# X_TRACK_PWR_V3_1.net
KiCad netlist of a schematic drawn in Altium Designer
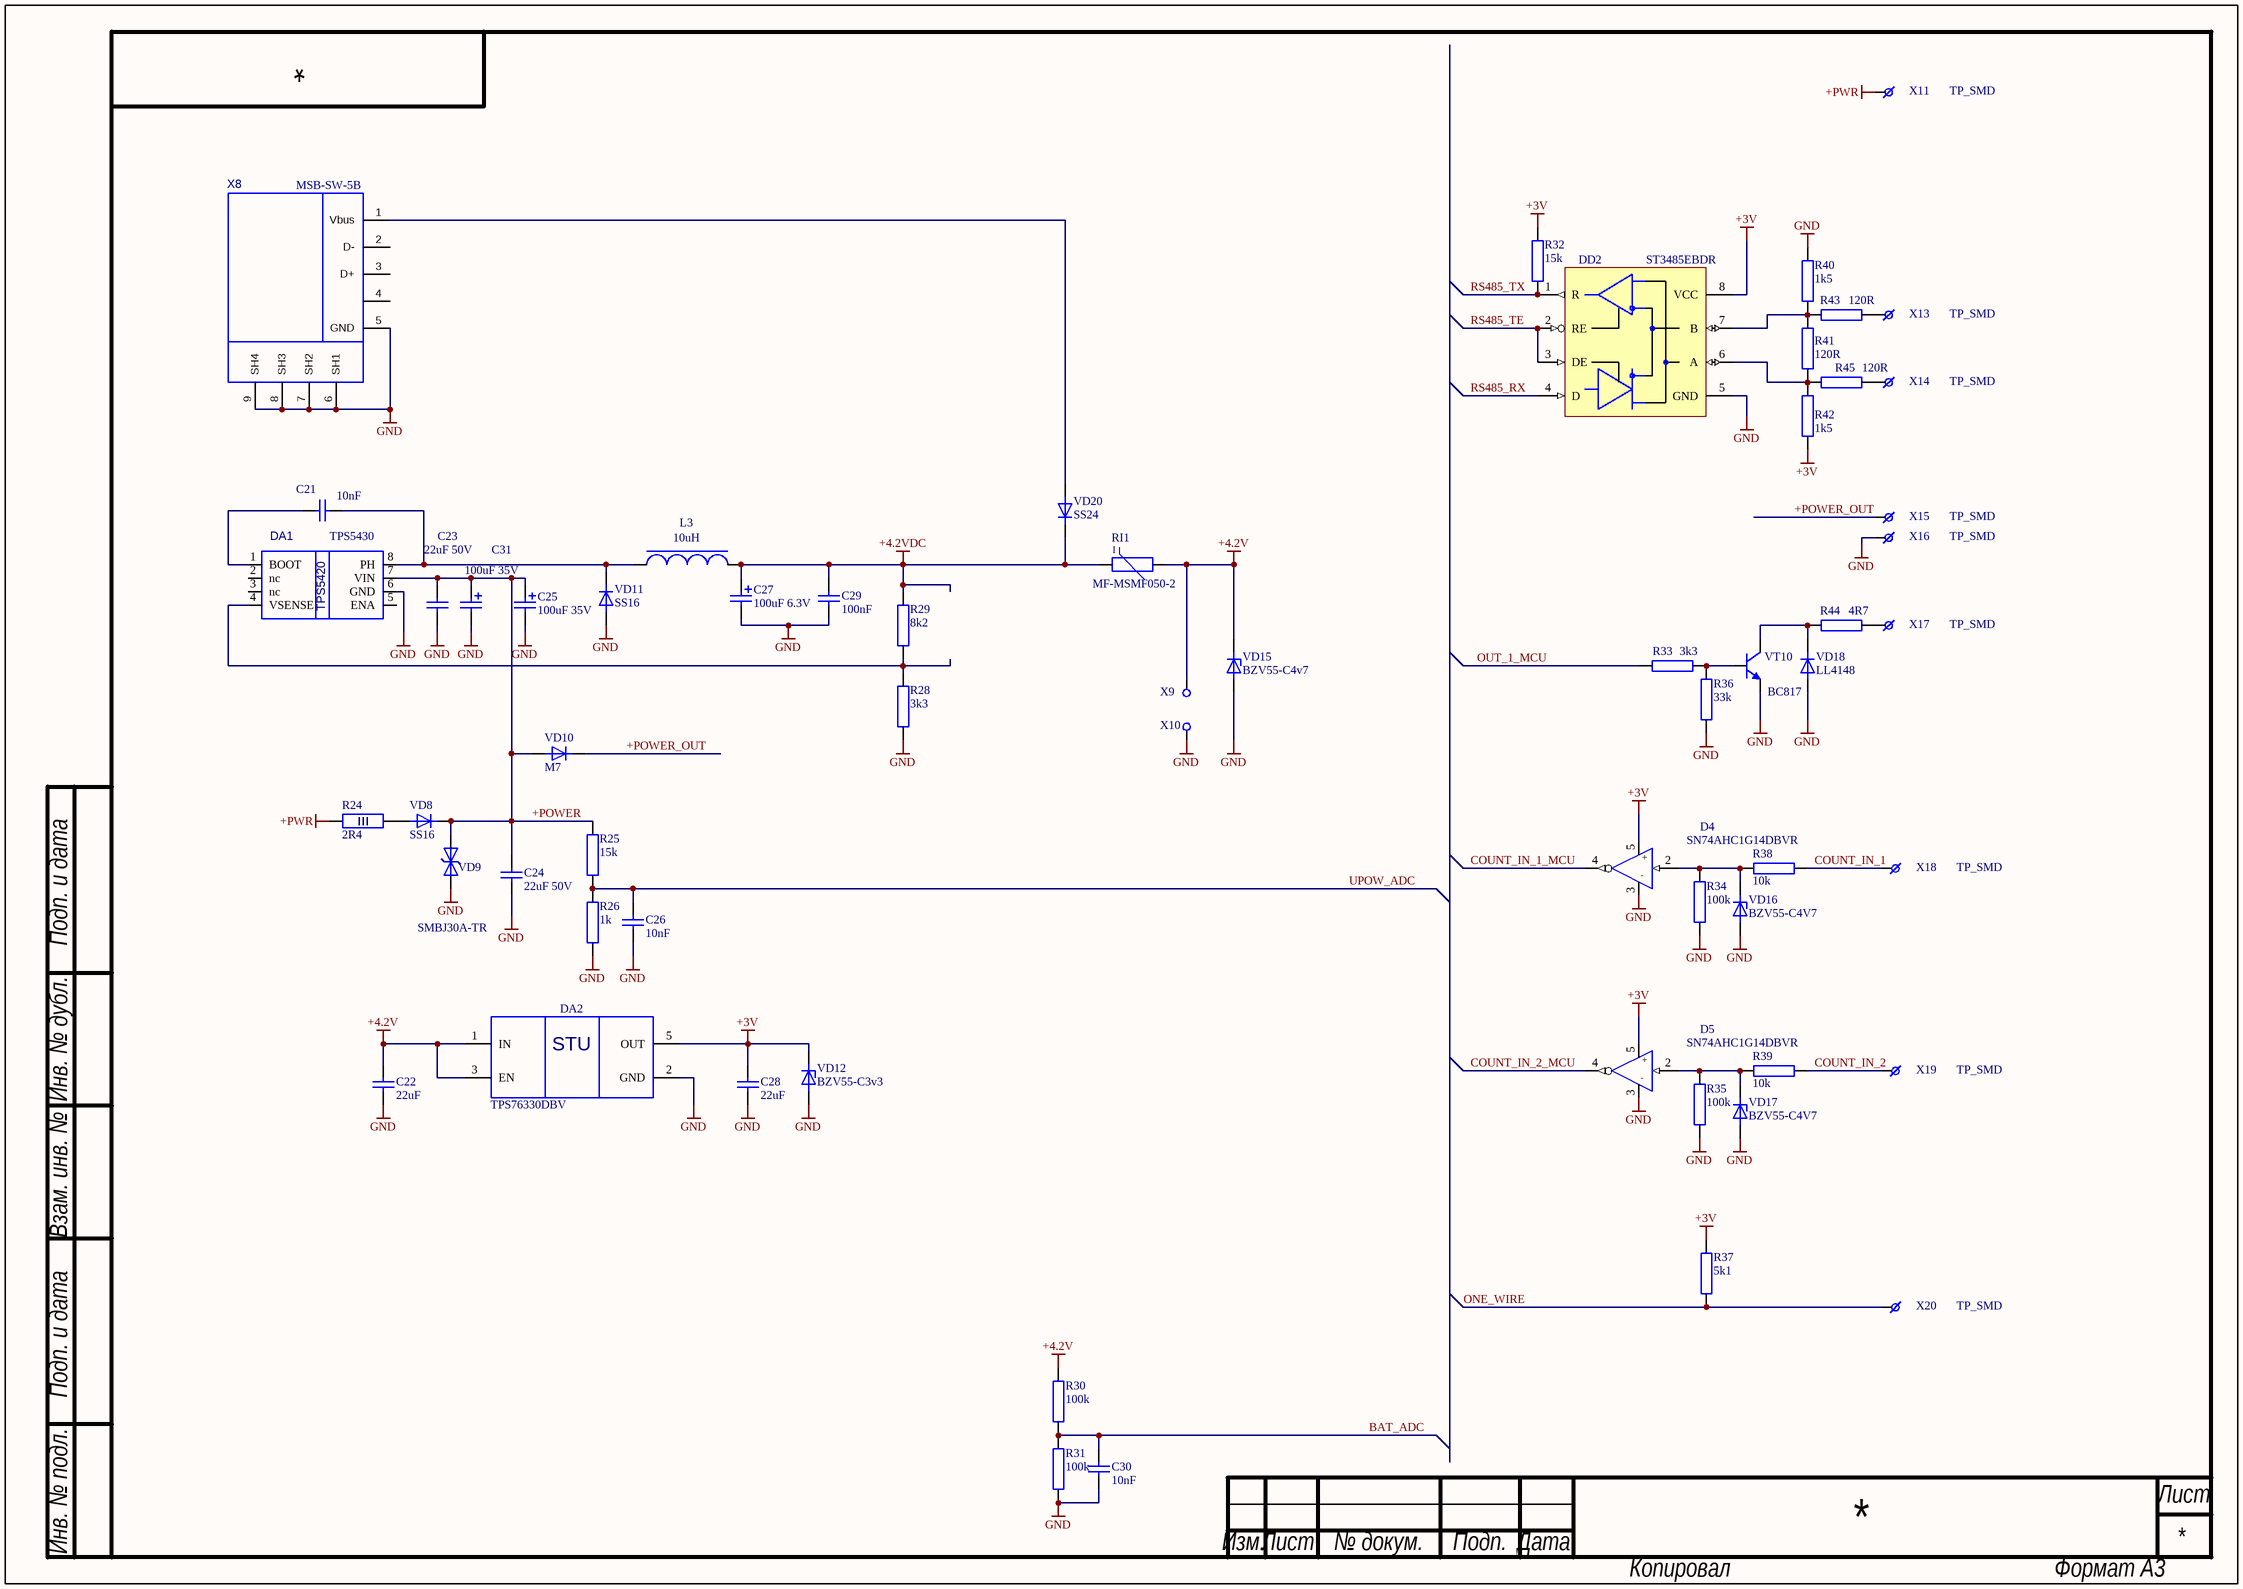
[diagram p0: X_TRACK_PWR V3.1.SchDoc]

(export (version "E")
  (design (tool "Eeschema 10.0.6"))
  (components
    (comp (ref "C21")
      (value "10nF")
      (footprint "CC0603")
      (description "Capacitor SMD 0603 X7R 10nF 20% 50V")
      (fields (field (name "MANUFACTURER") "Hitano") (field (name "Comment") "CC0603_10nF"))
      (libsource (lib "Ethernet_new_v000") (part "CC0603_10nF"))
    )
    (comp (ref "C22")
      (value "22uF")
      (footprint "CC0805")
      (description "Capacitor SMD 0805 Y5V 10uF 20% 16V")
      (fields (field (name "MANUFACTURER") "Hitano") (field (name "Comment") "CC0805_10uF"))
      (libsource (lib "Ethernet_new_v000") (part "CC0805_10uF"))
    )
    (comp (ref "C23")
      (value "22uF 50V")
      (footprint "CC1206")
      (description "Capacitor SMD 1206 X5R 10uF 20% 50V")
      (fields (field (name "MANUFACTURER") "Hitano") (field (name "Comment") "CC1206_10uF"))
      (libsource (lib "Ethernet_new_v000") (part "CC1206_10uF"))
    )
    (comp (ref "C24")
      (value "22uF 50V")
      (footprint "CC1206")
      (description "Capacitor SMD 1206 X5R 10uF 20% 50V")
      (fields (field (name "MANUFACTURER") "Hitano") (field (name "Comment") "CC1206_10uF"))
      (libsource (lib "Ethernet_new_v000") (part "CC1206_10uF"))
    )
    (comp (ref "C25")
      (value "100uF 35V")
      (footprint "CAPPR2.5-6.3X11.5 - HR")
      (description "Standard Capacitor polarized Radial leads, cylindrical aluminum case,")
      (fields (field (name "MANUFACTURER") "Hitano") (field (name "Comment") "C_ECR_100uF 35V_(D6)"))
      (libsource (lib "Ethernet_new_v000") (part "C_ECR_100uF 35V_(D6)"))
    )
    (comp (ref "C26")
      (value "10nF")
      (footprint "CC0603")
      (description "Capacitor SMD 0603 X7R 10nF 20% 50V")
      (fields (field (name "MANUFACTURER") "Hitano") (field (name "Comment") "CC0603_10nF"))
      (libsource (lib "Ethernet_new_v000") (part "CC0603_10nF"))
    )
    (comp (ref "C27")
      (value "100uF 6.3V")
      (footprint "6032_TC")
      (description "Capacitor tantall")
      (fields (field (name "MANUFACTURER") "AVX") (field (name "Comment") "C_TAJ 100uF 6.3V C"))
      (libsource (lib "Ethernet_new_v000") (part "C_TAJ 100uF 6.3V C"))
    )
    (comp (ref "C28")
      (value "22uF")
      (footprint "CC0805")
      (description "Capacitor SMD 0805 Y5V 10uF 20% 16V")
      (fields (field (name "MANUFACTURER") "Hitano") (field (name "Comment") "CC0805_10uF"))
      (libsource (lib "Ethernet_new_v000") (part "CC0805_10uF"))
    )
    (comp (ref "C29")
      (value "100nF")
      (footprint "CC0603")
      (description "Capacitor SMD 0603 X7R 100nF 20% 50V")
      (fields (field (name "MANUFACTURER") "Hitano") (field (name "Comment") "CC0603_100nF"))
      (libsource (lib "Ethernet_new_v000") (part "CC0603_100nF"))
    )
    (comp (ref "C30")
      (value "10nF")
      (footprint "CC0603")
      (description "Capacitor SMD 0603 X7R 10nF 20% 50V")
      (fields (field (name "MANUFACTURER") "Hitano") (field (name "Comment") "CC0603_10nF"))
      (libsource (lib "Ethernet_new_v000") (part "CC0603_10nF"))
    )
    (comp (ref "C31")
      (value "100uF 35V")
      (footprint "CAPPR2.5-6.3X11.5 - HL")
      (description "Standard Capacitor polarized Radial leads, cylindrical aluminum case,")
      (fields (field (name "MANUFACTURER") "Hitano") (field (name "Comment") "C_ECR_100uF 35V_(D6)"))
      (libsource (lib "Ethernet_new_v000") (part "C_ECR_100uF 35V_(D6)"))
    )
    (comp (ref "D4")
      (value "SN74AHC1G14DBVR")
      (footprint "SOT23-5AN")
      (description "SINGLE  SCHMITT-TRIGGER  INVERTER  GATE")
      (fields (field (name "MANUFACTURER") "Texas  Instruments"))
      (libsource (lib "Ethernet_new_v000") (part "SN74AHC1G14DBVR"))
    )
    (comp (ref "D5")
      (value "SN74AHC1G14DBVR")
      (footprint "SOT23-5AN")
      (description "SINGLE  SCHMITT-TRIGGER  INVERTER  GATE")
      (fields (field (name "MANUFACTURER") "Texas  Instruments"))
      (libsource (lib "Ethernet_new_v000") (part "SN74AHC1G14DBVR"))
    )
    (comp (ref "DA1")
      (value "TPS5430")
      (footprint "SO8")
      (description "TPS5420")
      (libsource (lib "V1.5") (part "TPS5420"))
    )
    (comp (ref "DA2")
      (value "TPS76330DBV")
      (footprint "SOT23-5")
      (libsource (lib "V1.5") (part "TPS76330DBV"))
    )
    (comp (ref "DD2")
      (value "ST3485EBDR")
      (footprint "8S1_L")
      (description "DRIVER RS-422/DIFFERENTIAL DRIVER AND RECEIVER PAIR")
      (fields (field (name "Comment") "SN75176"))
      (libsource (lib "Ethernet_new_v000") (part "SN75176"))
    )
    (comp (ref "L3")
      (value "10uH")
      (footprint "CDRH6D38")
      (description "CDRH6D38")
      (libsource (lib "V1.5") (part "CDRH6D38"))
    )
    (comp (ref "R24")
      (value "2R4")
      (footprint "MFR300- 3W-23-17.5X6.5")
      (description "Resistor  axial 3W")
      (fields (field (name "MANUFACTURER") "Uni-ohm") (field (name "Comment") "R_MFR03W"))
      (libsource (lib "Ethernet_new_v000") (part "R_MFR03W"))
    )
    (comp (ref "R25")
      (value "15k")
      (footprint "RC0603")
      (description "Resistor  SMD RC0603 5% 15k")
      (fields (field (name "MANUFACTURER") "Hitano") (field (name "Comment") "RC0603 15k"))
      (libsource (lib "Ethernet_new_v000") (part "RC0603 15k"))
    )
    (comp (ref "R26")
      (value "1k")
      (footprint "RC0603")
      (description "Resistor  SMD 0603  5% 1k")
      (fields (field (name "MANUFACTURER") "Hitano") (field (name "Comment") "RC0603 1k"))
      (libsource (lib "Ethernet_new_v000") (part "RC0603 1k"))
    )
    (comp (ref "R28")
      (value "3k3")
      (footprint "RC0603")
      (description "Resistor  SMD 0603  5% 3k3")
      (fields (field (name "MANUFACTURER") "Hitano") (field (name "Comment") "RC0603 3k3"))
      (libsource (lib "Ethernet_new_v000") (part "RC0603 3k3"))
    )
    (comp (ref "R29")
      (value "8k2")
      (footprint "RC0603")
      (description "Resistor  SMD 0603  5% 8k2")
      (fields (field (name "MANUFACTURER") "Hitano") (field (name "Comment") "RC0603 8k2"))
      (libsource (lib "Ethernet_new_v000") (part "RC0603 8k2"))
    )
    (comp (ref "R30")
      (value "100k")
      (footprint "RC0603")
      (description "Resistor  SMD 0603 5% 100k")
      (fields (field (name "MANUFACTURER") "Hitano") (field (name "Comment") "RC0603 100k"))
      (libsource (lib "Ethernet_new_v000") (part "RC0603 100k"))
    )
    (comp (ref "R31")
      (value "100k")
      (footprint "RC0603")
      (description "Resistor  SMD 0603 5% 100k")
      (fields (field (name "MANUFACTURER") "Hitano") (field (name "Comment") "RC0603 100k"))
      (libsource (lib "Ethernet_new_v000") (part "RC0603 100k"))
    )
    (comp (ref "R32")
      (value "15k")
      (footprint "RC0603")
      (description "Resistor  SMD RC0603 5% 15k")
      (fields (field (name "MANUFACTURER") "Hitano") (field (name "Comment") "RC0603 15k"))
      (libsource (lib "Ethernet_new_v000") (part "RC0603 15k"))
    )
    (comp (ref "R33")
      (value "3k3")
      (footprint "RC0603")
      (description "Resistor  SMD 0603  5% 3k3")
      (fields (field (name "MANUFACTURER") "Hitano") (field (name "Comment") "RC0603 3k3"))
      (libsource (lib "Ethernet_new_v000") (part "RC0603 3k3"))
    )
    (comp (ref "R34")
      (value "100k")
      (footprint "RC0603")
      (description "Resistor  SMD 0603 5% 100k")
      (fields (field (name "MANUFACTURER") "Hitano") (field (name "Comment") "RC0603 100k"))
      (libsource (lib "Ethernet_new_v000") (part "RC0603 100k"))
    )
    (comp (ref "R35")
      (value "100k")
      (footprint "RC0603")
      (description "Resistor  SMD 0603 5% 100k")
      (fields (field (name "MANUFACTURER") "Hitano") (field (name "Comment") "RC0603 100k"))
      (libsource (lib "Ethernet_new_v000") (part "RC0603 100k"))
    )
    (comp (ref "R36")
      (value "33k")
      (footprint "RC0603")
      (description "Resistor  SMD 0603 5% 33k")
      (fields (field (name "MANUFACTURER") "Hitano") (field (name "Comment") "RC0603 33k"))
      (libsource (lib "Ethernet_new_v000") (part "RC0603 33k"))
    )
    (comp (ref "R37")
      (value "5k1")
      (footprint "RC0603")
      (description "Resistor  SMD 0603 5% 5k1")
      (fields (field (name "MANUFACTURER") "Hitano") (field (name "Comment") "RC0603 5k1"))
      (libsource (lib "Ethernet_new_v000") (part "RC0603 5k1"))
    )
    (comp (ref "R38")
      (value "10k")
      (footprint "RC0603")
      (description "Resistor  SMD 0603 5% 4k7")
      (fields (field (name "MANUFACTURER") "Hitano") (field (name "Comment") "RC0603 4k7"))
      (libsource (lib "Ethernet_new_v000") (part "RC0603 4k7"))
    )
    (comp (ref "R39")
      (value "10k")
      (footprint "RC0603")
      (description "Resistor  SMD 0603 5% 4k7")
      (fields (field (name "MANUFACTURER") "Hitano") (field (name "Comment") "RC0603 4k7"))
      (libsource (lib "Ethernet_new_v000") (part "RC0603 4k7"))
    )
    (comp (ref "R40")
      (value "1k5")
      (footprint "RC0603")
      (description "Resistor  SMD 0603  5% 1k5")
      (fields (field (name "MANUFACTURER") "Hitano") (field (name "Comment") "RC0603 1k5"))
      (libsource (lib "Ethernet_new_v000") (part "RC0603 1k5"))
    )
    (comp (ref "R41")
      (value "120R")
      (footprint "RC0603")
      (description "Resistor  SMD 0603 5% 120R")
      (fields (field (name "MANUFACTURER") "Hitano") (field (name "Comment") "RC0603 120R"))
      (libsource (lib "Ethernet_new_v000") (part "RC0603 120R"))
    )
    (comp (ref "R42")
      (value "1k5")
      (footprint "RC0603")
      (description "Resistor  SMD 0603  5% 1k5")
      (fields (field (name "MANUFACTURER") "Hitano") (field (name "Comment") "RC0603 1k5"))
      (libsource (lib "Ethernet_new_v000") (part "RC0603 1k5"))
    )
    (comp (ref "R43")
      (value "120R")
      (footprint "RC0603")
      (description "Resistor  SMD 0603 5% 120R")
      (fields (field (name "MANUFACTURER") "Hitano") (field (name "Comment") "RC0603 120R"))
      (libsource (lib "Ethernet_new_v000") (part "RC0603 120R"))
    )
    (comp (ref "R44")
      (value "4R7")
      (footprint "RC0603")
      (description "Resistor  SMD 0603 5% 10R")
      (fields (field (name "MANUFACTURER") "Hitano") (field (name "Comment") "RC0603 10R"))
      (libsource (lib "Ethernet_new_v000") (part "RC0603 10R"))
    )
    (comp (ref "R45")
      (value "120R")
      (footprint "RC0603")
      (description "Resistor  SMD 0603 5% 120R")
      (fields (field (name "MANUFACTURER") "Hitano") (field (name "Comment") "RC0603 120R"))
      (libsource (lib "Ethernet_new_v000") (part "RC0603 120R"))
    )
    (comp (ref "RI1")
      (value "MF-MSMF050-2")
      (footprint "FSMD1812 Series")
      (description "Polymeric PTC resettable fuses")
      (fields (field (name "MANUFACTURER") "Fuzetech") (field (name "Comment") "POLY_PTS"))
      (libsource (lib "Ethernet_new_v000") (part "FSMD110-16"))
    )
    (comp (ref "VD8")
      (value "SS16")
      (footprint "SMA/DO-214AC")
      (description "SURFACE MOUNT GENERAL RECTIFIER")
      (fields (field (name "MANUFACTURER") "Suntan Technology Company Limited") (field (name "Comment") "M7"))
      (libsource (lib "Ethernet_new_v000") (part "M7"))
    )
    (comp (ref "VD9")
      (value "SMBJ30A-TR")
      (footprint "SMB/DO-214AA")
      (description "TRANSIENT VOLTAGE SUPPRESSORS")
      (fields (field (name "Comment") "Suppressor"))
      (libsource (lib "Ethernet_new_v000") (part "Suppressor"))
    )
    (comp (ref "VD10")
      (value "M7")
      (footprint "SMA/DO-214AC")
      (description "SURFACE MOUNT GENERAL RECTIFIER")
      (fields (field (name "MANUFACTURER") "Suntan Technology Company Limited"))
      (libsource (lib "Ethernet_new_v000") (part "M7"))
    )
    (comp (ref "VD11")
      (value "SS16")
      (footprint "SMB/DO-214AA")
      (description "SMD Diod 2A 40V")
      (fields (field (name "MANUFACTURER") "Vishay Semiconductors") (field (name "Comment") "SS24"))
      (libsource (lib "Ethernet_new_v000") (part "SS24"))
    )
    (comp (ref "VD12")
      (value "BZV55-C3v3")
      (footprint "SOD80D_C")
      (description "Zener diode")
      (fields (field (name "MANUFACTURER") "Philips") (field (name "Comment") "Zener"))
      (libsource (lib "Ethernet_new_v000") (part "Zener"))
    )
    (comp (ref "VD15")
      (value "BZV55-C4v7")
      (footprint "SOD80D_C")
      (description "Zener diode")
      (fields (field (name "MANUFACTURER") "Philips") (field (name "Comment") "Zener"))
      (libsource (lib "Ethernet_new_v000") (part "Zener"))
    )
    (comp (ref "VD16")
      (value "BZV55-C4V7")
      (footprint "SOD80D_C")
      (description "Zener diode")
      (fields (field (name "MANUFACTURER") "Philips") (field (name "Comment") "Zener"))
      (libsource (lib "Ethernet_new_v000") (part "Zener"))
    )
    (comp (ref "VD17")
      (value "BZV55-C4V7")
      (footprint "SOD80D_C")
      (description "Zener diode")
      (fields (field (name "MANUFACTURER") "Philips") (field (name "Comment") "Zener"))
      (libsource (lib "Ethernet_new_v000") (part "Zener"))
    )
    (comp (ref "VD18")
      (value "LL4148")
      (footprint "SOD80D_C")
      (description "SMD Diod LL4148")
      (fields (field (name "MANUFACTURER") "Fairchild Semiconductor"))
      (libsource (lib "Ethernet_new_v000") (part "LL4148"))
    )
    (comp (ref "VD20")
      (value "SS24")
      (footprint "SMB/DO-214AA")
      (description "SMD Diod 2A 40V")
      (fields (field (name "MANUFACTURER") "Vishay Semiconductors"))
      (libsource (lib "Ethernet_new_v000") (part "SS24"))
    )
    (comp (ref "VT10")
      (value "BC817")
      (footprint "SOT23")
      (description "NPN general-purpose transistors, 45V, 500mA")
      (fields (field (name "MANUFACTURER") "Philips"))
      (libsource (lib "Ethernet_new_v000") (part "BC817"))
    )
    (comp (ref "X8") (value "MSB-SW-5B") (footprint "MSB-SW-5B") (libsource (lib "V1.5") (part "MSB-SW-5B")))
    (comp (ref "X9")
      (value "Con 1")
      (footprint "TP_1/2")
      (description "Contact")
      (libsource (lib "Ethernet_new_v000") (part "Con 1"))
    )
    (comp (ref "X10")
      (value "Con 1")
      (footprint "TP_1/2")
      (description "Contact")
      (libsource (lib "Ethernet_new_v000") (part "Con 1"))
    )
    (comp (ref "X11")
      (value "TP_SMD")
      (footprint "TP_1.5/2.5")
      (description "Contact")
      (fields (field (name "Comment") "Con_1"))
      (libsource (lib "Ethernet_new_v000") (part "Con_1"))
    )
    (comp (ref "X13")
      (value "TP_SMD")
      (footprint "TP_1/2")
      (description "Contact")
      (fields (field (name "Comment") "Con_1"))
      (libsource (lib "Ethernet_new_v000") (part "Con_1"))
    )
    (comp (ref "X14")
      (value "TP_SMD")
      (footprint "TP_1/2")
      (description "Contact")
      (fields (field (name "Comment") "Con_1"))
      (libsource (lib "Ethernet_new_v000") (part "Con_1"))
    )
    (comp (ref "X15")
      (value "TP_SMD")
      (footprint "TP_1/2")
      (description "Contact")
      (fields (field (name "Comment") "Con_1"))
      (libsource (lib "Ethernet_new_v000") (part "Con_1"))
    )
    (comp (ref "X16")
      (value "TP_SMD")
      (footprint "TP_1/2")
      (description "Contact")
      (fields (field (name "Comment") "Con_1"))
      (libsource (lib "Ethernet_new_v000") (part "Con_1"))
    )
    (comp (ref "X17")
      (value "TP_SMD")
      (footprint "TP_1/2")
      (description "Contact")
      (fields (field (name "Comment") "Con_1"))
      (libsource (lib "Ethernet_new_v000") (part "Con_1"))
    )
    (comp (ref "X18")
      (value "TP_SMD")
      (footprint "TP_1/2")
      (description "Contact")
      (fields (field (name "Comment") "Con_1"))
      (libsource (lib "Ethernet_new_v000") (part "Con_1"))
    )
    (comp (ref "X19")
      (value "TP_SMD")
      (footprint "TP_1/2")
      (description "Contact")
      (fields (field (name "Comment") "Con_1"))
      (libsource (lib "Ethernet_new_v000") (part "Con_1"))
    )
    (comp (ref "X20")
      (value "TP_SMD")
      (footprint "TP_1/2")
      (description "Contact")
      (fields (field (name "Comment") "Con_1"))
      (libsource (lib "Ethernet_new_v000") (part "Con_1"))
    )
  )
  (nets
    (net (code "1") (name "+3V") (class "Default")
      (node (ref "C28") (pin "2") (pinfunction "2_2") (pintype "passive"))
      (node (ref "D4") (pin "5") (pinfunction "+V_5") (pintype "power_in"))
      (node (ref "D5") (pin "5") (pinfunction "+V_5") (pintype "power_in"))
      (node (ref "DA2") (pin "5") (pinfunction "OUT_5") (pintype "passive"))
      (node (ref "DD2") (pin "8") (pinfunction "VCC_8") (pintype "power_in"))
      (node (ref "R32") (pin "2") (pinfunction "2_2") (pintype "passive"))
      (node (ref "R37") (pin "2") (pinfunction "2_2") (pintype "passive"))
      (node (ref "R42") (pin "1") (pinfunction "1_1") (pintype "passive"))
      (node (ref "VD12") (pin "2") (pinfunction "K_2") (pintype "passive"))
    )
    (net (code "2") (name "+4.2V") (class "Default")
      (node (ref "C22") (pin "2") (pinfunction "2_2") (pintype "passive"))
      (node (ref "DA2") (pin "1") (pinfunction "IN_1") (pintype "passive"))
      (node (ref "DA2") (pin "3") (pinfunction "EN_3") (pintype "passive"))
      (node (ref "R30") (pin "2") (pinfunction "2_2") (pintype "passive"))
      (node (ref "RI1") (pin "1") (pinfunction "1_1") (pintype "passive"))
      (node (ref "VD15") (pin "2") (pinfunction "K_2") (pintype "passive"))
      (node (ref "X9") (pin "1") (pinfunction "1_1") (pintype "passive"))
    )
    (net (code "3") (name "+4.2VDC") (class "Default")
      (node (ref "C27") (pin "1") (pinfunction "1_1") (pintype "passive"))
      (node (ref "C29") (pin "1") (pinfunction "1_1") (pintype "passive"))
      (node (ref "L3") (pin "2") (pinfunction "2_2") (pintype "passive"))
      (node (ref "R29") (pin "2") (pinfunction "2_2") (pintype "passive"))
      (node (ref "RI1") (pin "2") (pinfunction "2_2") (pintype "passive"))
      (node (ref "VD20") (pin "2") (pinfunction "K_2") (pintype "passive"))
    )
    (net (code "4") (name "+PWR") (class "Default")
      (node (ref "R24") (pin "1") (pinfunction "1_1") (pintype "passive"))
      (node (ref "X11") (pin "1") (pinfunction "1_1") (pintype "passive"))
    )
    (net (code "5") (name "/+POWER") (class "Default")
      (node (ref "C23") (pin "2") (pinfunction "2_2") (pintype "passive"))
      (node (ref "C24") (pin "2") (pinfunction "2_2") (pintype "passive"))
      (node (ref "C25") (pin "1") (pinfunction "1_1") (pintype "passive"))
      (node (ref "C31") (pin "1") (pinfunction "1_1") (pintype "passive"))
      (node (ref "DA1") (pin "7") (pinfunction "VIN_7") (pintype "passive"))
      (node (ref "R25") (pin "2") (pinfunction "2_2") (pintype "passive"))
      (node (ref "VD10") (pin "1") (pinfunction "A_1") (pintype "passive"))
      (node (ref "VD8") (pin "2") (pinfunction "K_2") (pintype "passive"))
      (node (ref "VD9") (pin "2") (pinfunction "K_2") (pintype "passive"))
    )
    (net (code "6") (name "/+POWER_OUT") (class "Default")
      (node (ref "VD10") (pin "2") (pinfunction "K_2") (pintype "passive"))
      (node (ref "X15") (pin "1") (pinfunction "1_1") (pintype "passive"))
    )
    (net (code "7") (name "/BAT_ADC") (class "Default")
      (node (ref "C30") (pin "2") (pinfunction "2_2") (pintype "passive"))
      (node (ref "R30") (pin "1") (pinfunction "1_1") (pintype "passive"))
      (node (ref "R31") (pin "2") (pinfunction "2_2") (pintype "passive"))
    )
    (net (code "8") (name "/COUNT_IN_1") (class "Default")
      (node (ref "R38") (pin "1") (pinfunction "1_1") (pintype "passive"))
      (node (ref "X18") (pin "1") (pinfunction "1_1") (pintype "passive"))
    )
    (net (code "9") (name "/COUNT_IN_1_MCU") (class "Default")
      (node (ref "D4") (pin "4") (pinfunction "Y_4") (pintype "output"))
    )
    (net (code "10") (name "/COUNT_IN_2") (class "Default")
      (node (ref "R39") (pin "1") (pinfunction "1_1") (pintype "passive"))
      (node (ref "X19") (pin "1") (pinfunction "1_1") (pintype "passive"))
    )
    (net (code "11") (name "/COUNT_IN_2_MCU") (class "Default")
      (node (ref "D5") (pin "4") (pinfunction "Y_4") (pintype "output"))
    )
    (net (code "12") (name "/ONE_WIRE") (class "Default")
      (node (ref "R37") (pin "1") (pinfunction "1_1") (pintype "passive"))
      (node (ref "X20") (pin "1") (pinfunction "1_1") (pintype "passive"))
    )
    (net (code "13") (name "/OUT_1_MCU") (class "Default")
      (node (ref "R33") (pin "1") (pinfunction "1_1") (pintype "passive"))
    )
    (net (code "14") (name "/RS485_RX") (class "Default")
      (node (ref "DD2") (pin "4") (pinfunction "D_4") (pintype "input"))
    )
    (net (code "15") (name "/RS485_TE") (class "Default")
      (node (ref "DD2") (pin "2") (pinfunction "RE_2") (pintype "input"))
      (node (ref "DD2") (pin "3") (pinfunction "DE_3") (pintype "input"))
    )
    (net (code "16") (name "/RS485_TX") (class "Default")
      (node (ref "DD2") (pin "1") (pinfunction "R_1") (pintype "output"))
      (node (ref "R32") (pin "1") (pinfunction "1_1") (pintype "passive"))
    )
    (net (code "17") (name "/UPOW_ADC") (class "Default")
      (node (ref "C26") (pin "2") (pinfunction "2_2") (pintype "passive"))
      (node (ref "R25") (pin "1") (pinfunction "1_1") (pintype "passive"))
      (node (ref "R26") (pin "2") (pinfunction "2_2") (pintype "passive"))
    )
    (net (code "18") (name "GND") (class "Default")
      (node (ref "C22") (pin "1") (pinfunction "1_1") (pintype "passive"))
      (node (ref "C23") (pin "1") (pinfunction "1_1") (pintype "passive"))
      (node (ref "C24") (pin "1") (pinfunction "1_1") (pintype "passive"))
      (node (ref "C25") (pin "2") (pinfunction "2_2") (pintype "passive"))
      (node (ref "C26") (pin "1") (pinfunction "1_1") (pintype "passive"))
      (node (ref "C27") (pin "2") (pinfunction "2_2") (pintype "passive"))
      (node (ref "C28") (pin "1") (pinfunction "1_1") (pintype "passive"))
      (node (ref "C29") (pin "2") (pinfunction "2_2") (pintype "passive"))
      (node (ref "C30") (pin "1") (pinfunction "1_1") (pintype "passive"))
      (node (ref "C31") (pin "2") (pinfunction "2_2") (pintype "passive"))
      (node (ref "D4") (pin "3") (pinfunction "GND_3") (pintype "power_in"))
      (node (ref "D5") (pin "3") (pinfunction "GND_3") (pintype "power_in"))
      (node (ref "DA1") (pin "6") (pinfunction "GND_6") (pintype "passive"))
      (node (ref "DA2") (pin "2") (pinfunction "GND_2") (pintype "passive"))
      (node (ref "DD2") (pin "5") (pinfunction "GND_5") (pintype "power_in"))
      (node (ref "R26") (pin "1") (pinfunction "1_1") (pintype "passive"))
      (node (ref "R28") (pin "1") (pinfunction "1_1") (pintype "passive"))
      (node (ref "R31") (pin "1") (pinfunction "1_1") (pintype "passive"))
      (node (ref "R34") (pin "1") (pinfunction "1_1") (pintype "passive"))
      (node (ref "R35") (pin "1") (pinfunction "1_1") (pintype "passive"))
      (node (ref "R36") (pin "1") (pinfunction "1_1") (pintype "passive"))
      (node (ref "R40") (pin "2") (pinfunction "2_2") (pintype "passive"))
      (node (ref "VD11") (pin "1") (pinfunction "A_1") (pintype "passive"))
      (node (ref "VD12") (pin "1") (pinfunction "A_1") (pintype "passive"))
      (node (ref "VD15") (pin "1") (pinfunction "A_1") (pintype "passive"))
      (node (ref "VD16") (pin "1") (pinfunction "A_1") (pintype "passive"))
      (node (ref "VD17") (pin "1") (pinfunction "A_1") (pintype "passive"))
      (node (ref "VD18") (pin "1") (pinfunction "A_1") (pintype "passive"))
      (node (ref "VD9") (pin "1") (pinfunction "A_1") (pintype "passive"))
      (node (ref "VT10") (pin "2") (pinfunction "E_2") (pintype "passive"))
      (node (ref "X10") (pin "1") (pinfunction "1_1") (pintype "passive"))
      (node (ref "X16") (pin "1") (pinfunction "1_1") (pintype "passive"))
      (node (ref "X8") (pin "5") (pinfunction "GND_5") (pintype "passive"))
      (node (ref "X8") (pin "6") (pinfunction "SH1_6") (pintype "passive"))
      (node (ref "X8") (pin "7") (pinfunction "SH2_7") (pintype "passive"))
      (node (ref "X8") (pin "8") (pinfunction "SH3_8") (pintype "passive"))
      (node (ref "X8") (pin "9") (pinfunction "SH4_9") (pintype "passive"))
    )
    (net (code "19") (name "Net-(D4-A)") (class "Default")
      (node (ref "D4") (pin "2") (pinfunction "A_2") (pintype "input"))
      (node (ref "R34") (pin "2") (pinfunction "2_2") (pintype "passive"))
      (node (ref "R38") (pin "2") (pinfunction "2_2") (pintype "passive"))
      (node (ref "VD16") (pin "2") (pinfunction "K_2") (pintype "passive"))
    )
    (net (code "20") (name "Net-(D5-A)") (class "Default")
      (node (ref "D5") (pin "2") (pinfunction "A_2") (pintype "input"))
      (node (ref "R35") (pin "2") (pinfunction "2_2") (pintype "passive"))
      (node (ref "R39") (pin "2") (pinfunction "2_2") (pintype "passive"))
      (node (ref "VD17") (pin "2") (pinfunction "K_2") (pintype "passive"))
    )
    (net (code "21") (name "Net-(DA1-BOOT)") (class "Default")
      (node (ref "C21") (pin "1") (pinfunction "1_1") (pintype "passive"))
      (node (ref "DA1") (pin "1") (pinfunction "BOOT_1") (pintype "passive"))
    )
    (net (code "22") (name "Net-(DA1-PH)") (class "Default")
      (node (ref "C21") (pin "2") (pinfunction "2_2") (pintype "passive"))
      (node (ref "DA1") (pin "8") (pinfunction "PH_8") (pintype "passive"))
      (node (ref "L3") (pin "1") (pinfunction "1_1") (pintype "passive"))
      (node (ref "VD11") (pin "2") (pinfunction "K_2") (pintype "passive"))
    )
    (net (code "23") (name "Net-(DA1-VSENSE)") (class "Default")
      (node (ref "DA1") (pin "4") (pinfunction "VSENSE_4") (pintype "passive"))
      (node (ref "R28") (pin "2") (pinfunction "2_2") (pintype "passive"))
      (node (ref "R29") (pin "1") (pinfunction "1_1") (pintype "passive"))
    )
    (net (code "24") (name "Net-(DD2-A)") (class "Default")
      (node (ref "DD2") (pin "6") (pinfunction "A_6") (pintype "bidirectional"))
      (node (ref "R41") (pin "1") (pinfunction "1_1") (pintype "passive"))
      (node (ref "R42") (pin "2") (pinfunction "2_2") (pintype "passive"))
      (node (ref "R45") (pin "2") (pinfunction "2_2") (pintype "passive"))
    )
    (net (code "25") (name "Net-(DD2-B)") (class "Default")
      (node (ref "DD2") (pin "7") (pinfunction "B_7") (pintype "bidirectional"))
      (node (ref "R40") (pin "1") (pinfunction "1_1") (pintype "passive"))
      (node (ref "R41") (pin "2") (pinfunction "2_2") (pintype "passive"))
      (node (ref "R43") (pin "2") (pinfunction "2_2") (pintype "passive"))
    )
    (net (code "26") (name "Net-(R43-Pad1)") (class "Default")
      (node (ref "R43") (pin "1") (pinfunction "1_1") (pintype "passive"))
      (node (ref "X13") (pin "1") (pinfunction "1_1") (pintype "passive"))
    )
    (net (code "27") (name "Net-(R44-Pad1)") (class "Default")
      (node (ref "R44") (pin "1") (pinfunction "1_1") (pintype "passive"))
      (node (ref "X17") (pin "1") (pinfunction "1_1") (pintype "passive"))
    )
    (net (code "28") (name "Net-(R45-Pad1)") (class "Default")
      (node (ref "R45") (pin "1") (pinfunction "1_1") (pintype "passive"))
      (node (ref "X14") (pin "1") (pinfunction "1_1") (pintype "passive"))
    )
    (net (code "29") (name "Net-(VD8-A)") (class "Default")
      (node (ref "R24") (pin "2") (pinfunction "2_2") (pintype "passive"))
      (node (ref "VD8") (pin "1") (pinfunction "A_1") (pintype "passive"))
    )
    (net (code "30") (name "Net-(VD18-K)") (class "Default")
      (node (ref "R44") (pin "2") (pinfunction "2_2") (pintype "passive"))
      (node (ref "VD18") (pin "2") (pinfunction "K_2") (pintype "passive"))
      (node (ref "VT10") (pin "3") (pinfunction "C_3") (pintype "passive"))
    )
    (net (code "31") (name "Net-(VD20-A)") (class "Default")
      (node (ref "VD20") (pin "1") (pinfunction "A_1") (pintype "passive"))
      (node (ref "X8") (pin "1") (pinfunction "Vbus_1") (pintype "passive"))
    )
    (net (code "32") (name "Net-(VT10-B)") (class "Default")
      (node (ref "R33") (pin "2") (pinfunction "2_2") (pintype "passive"))
      (node (ref "R36") (pin "2") (pinfunction "2_2") (pintype "passive"))
      (node (ref "VT10") (pin "1") (pinfunction "B_1") (pintype "passive"))
    )
    (net (code "33") (name "unconnected-(DA1-ENA-Pad5)") (class "Default")
      (node (ref "DA1") (pin "5") (pinfunction "ENA_5") (pintype "passive"))
    )
    (net (code "34") (name "unconnected-(DA1-nc-Pad2)") (class "Default")
      (node (ref "DA1") (pin "2") (pinfunction "nc_2") (pintype "passive"))
    )
    (net (code "35") (name "unconnected-(DA1-nc-Pad3)") (class "Default")
      (node (ref "DA1") (pin "3") (pinfunction "nc_3") (pintype "passive"))
    )
    (net (code "36") (name "unconnected-(DA2-Pad4)") (class "Default")
      (node (ref "DA2") (pin "4") (pintype "passive"))
    )
    (net (code "37") (name "unconnected-(X8-D+-Pad3)") (class "Default")
      (node (ref "X8") (pin "3") (pinfunction "D+_3") (pintype "passive"))
    )
    (net (code "38") (name "unconnected-(X8-D--Pad2)") (class "Default")
      (node (ref "X8") (pin "2") (pinfunction "D-_2") (pintype "passive"))
    )
    (net (code "39") (name "unconnected-(X8-Pad4)") (class "Default")
      (node (ref "X8") (pin "4") (pintype "passive"))
    )
  )
)
